# 1u_panel_breakout.net
KiCad netlist of a schematic drawn in EAGLE
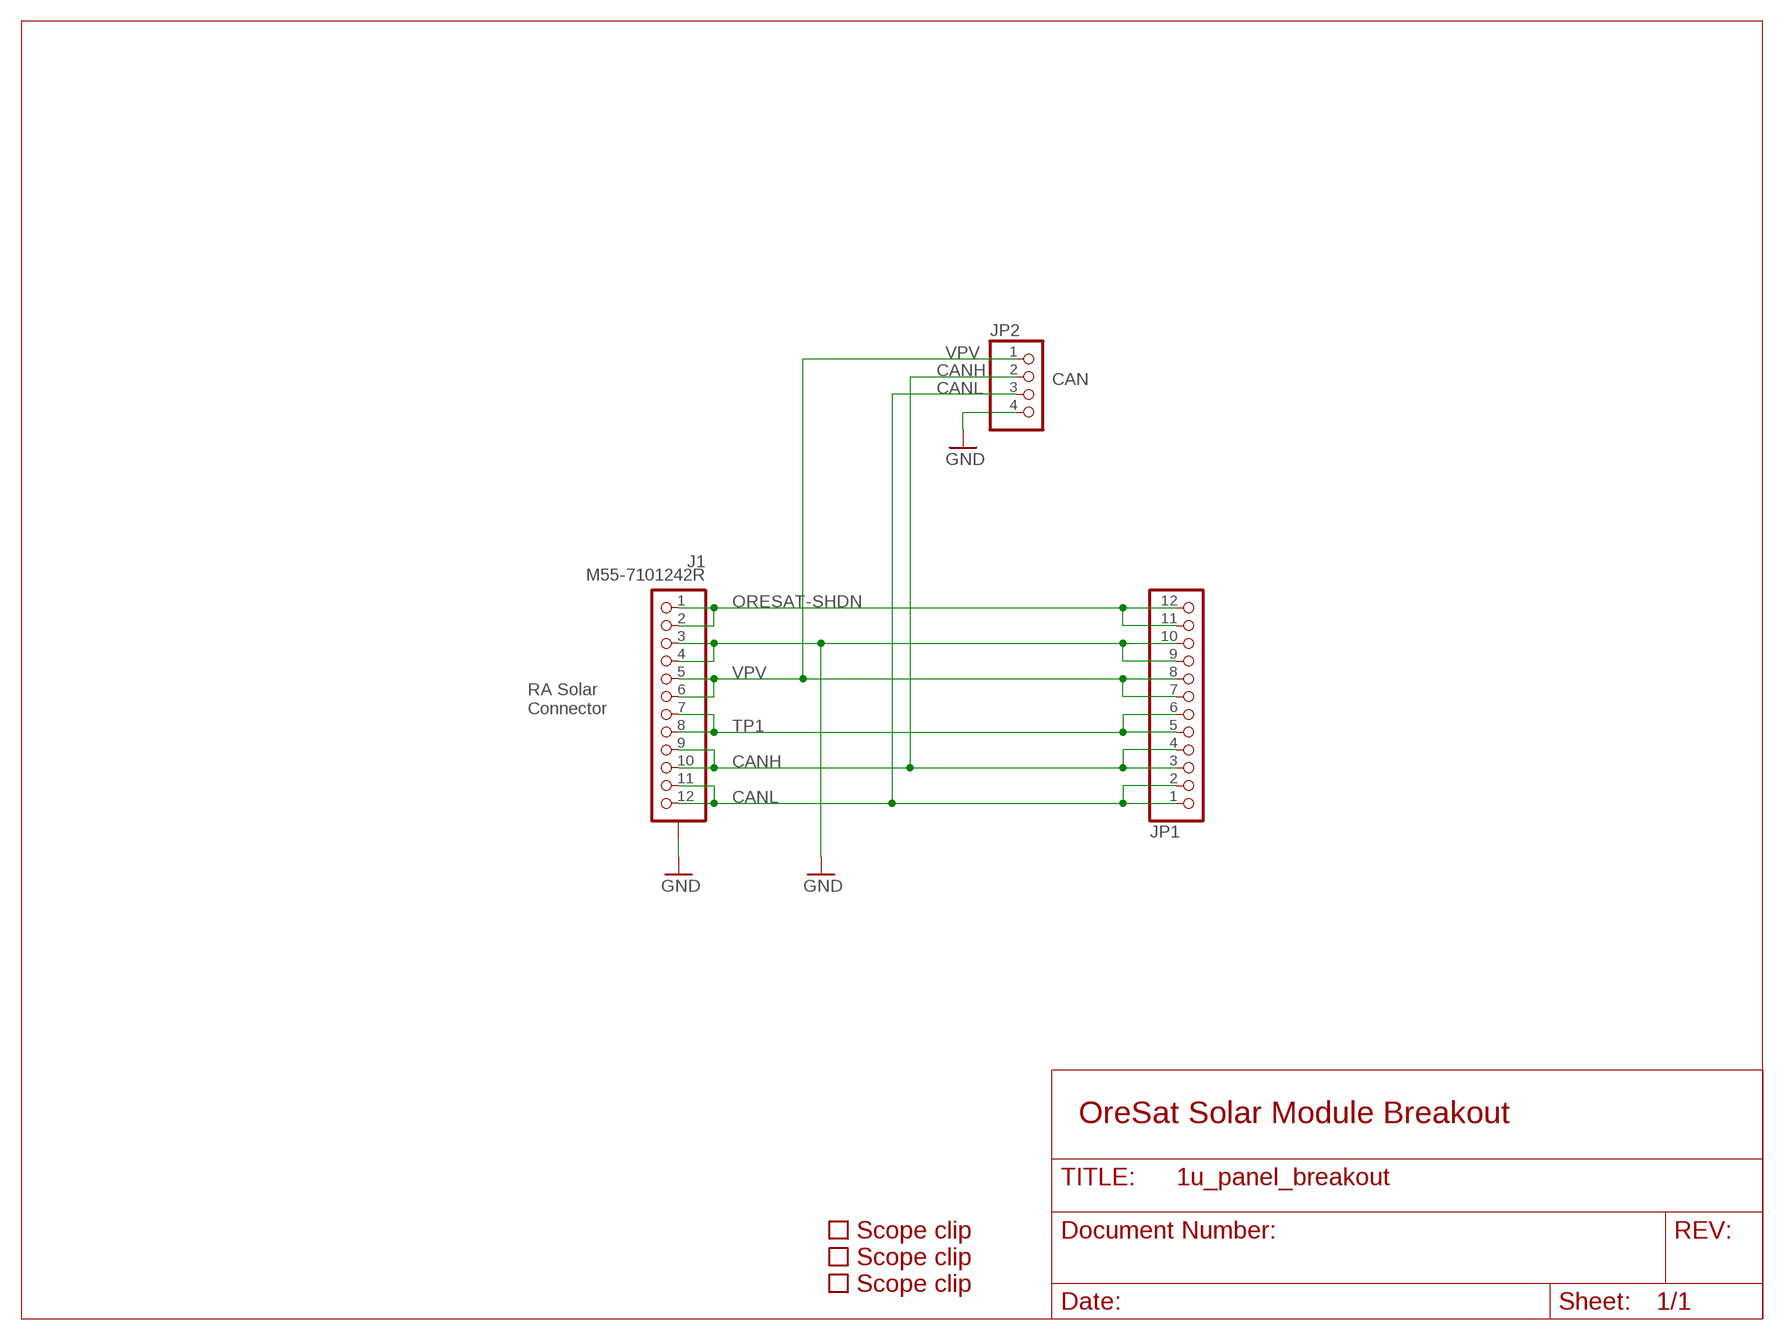
[diagram p0: schematic, sheet 1]

(export (version "E")
  (design (tool "Eeschema 10.0.6"))
  (components
    (comp (ref "J1")
      (value "M55-7101242R")
      (footprint "eagle-import:M55-7101242R")
      (libsource (lib "eagle-import") (part "M55-7101242R"))
    )
    (comp (ref "JP1")
      (value "PINHD-1X12")
      (footprint "eagle-import:1X12")
      (libsource (lib "eagle-import") (part "PINHD-1X12"))
    )
    (comp (ref "JP2")
      (value "PINHD-1X4")
      (footprint "eagle-import:1X04")
      (libsource (lib "eagle-import") (part "PINHD-1X4"))
    )
    (comp (ref "U$1")
      (value "SCOPE_CLIP")
      (footprint "eagle-import:SCOPE_CLIP")
      (libsource (lib "eagle-import") (part "SCOPE_CLIP"))
    )
    (comp (ref "U$2")
      (value "SCOPE_CLIP")
      (footprint "eagle-import:SCOPE_CLIP")
      (libsource (lib "eagle-import") (part "SCOPE_CLIP"))
    )
    (comp (ref "U$3")
      (value "SCOPE_CLIP")
      (footprint "eagle-import:SCOPE_CLIP")
      (libsource (lib "eagle-import") (part "SCOPE_CLIP"))
    )
  )
  (nets
    (net (code "1") (name "/CANH") (class "Default")
      (node (ref "J1") (pin "10") (pinfunction "10_10") (pintype "passive"))
      (node (ref "J1") (pin "9") (pinfunction "9_9") (pintype "passive"))
      (node (ref "JP1") (pin "3") (pinfunction "3_3") (pintype "passive"))
      (node (ref "JP1") (pin "4") (pinfunction "4_4") (pintype "passive"))
      (node (ref "JP2") (pin "2") (pinfunction "2_2") (pintype "passive"))
    )
    (net (code "2") (name "/CANL") (class "Default")
      (node (ref "J1") (pin "11") (pinfunction "11_11") (pintype "passive"))
      (node (ref "J1") (pin "12") (pinfunction "12_12") (pintype "passive"))
      (node (ref "JP1") (pin "1") (pinfunction "1_1") (pintype "passive"))
      (node (ref "JP1") (pin "2") (pinfunction "2_2") (pintype "passive"))
      (node (ref "JP2") (pin "3") (pinfunction "3_3") (pintype "passive"))
    )
    (net (code "3") (name "/ORESAT-SHDN") (class "Default")
      (node (ref "J1") (pin "1") (pinfunction "1_1") (pintype "passive"))
      (node (ref "J1") (pin "2") (pinfunction "2_2") (pintype "passive"))
      (node (ref "JP1") (pin "11") (pinfunction "11_11") (pintype "passive"))
      (node (ref "JP1") (pin "12") (pinfunction "12_12") (pintype "passive"))
    )
    (net (code "4") (name "/TP1") (class "Default")
      (node (ref "J1") (pin "7") (pinfunction "7_7") (pintype "passive"))
      (node (ref "J1") (pin "8") (pinfunction "8_8") (pintype "passive"))
      (node (ref "JP1") (pin "5") (pinfunction "5_5") (pintype "passive"))
      (node (ref "JP1") (pin "6") (pinfunction "6_6") (pintype "passive"))
    )
    (net (code "5") (name "/VPV") (class "Default")
      (node (ref "J1") (pin "5") (pinfunction "5_5") (pintype "passive"))
      (node (ref "J1") (pin "6") (pinfunction "6_6") (pintype "passive"))
      (node (ref "JP1") (pin "7") (pinfunction "7_7") (pintype "passive"))
      (node (ref "JP1") (pin "8") (pinfunction "8_8") (pintype "passive"))
      (node (ref "JP2") (pin "1") (pinfunction "1_1") (pintype "passive"))
    )
    (net (code "6") (name "GND") (class "Default")
      (node (ref "J1") (pin "3") (pinfunction "3_3") (pintype "passive"))
      (node (ref "J1") (pin "4") (pinfunction "4_4") (pintype "passive"))
      (node (ref "J1") (pin "P$1") (pinfunction "SHIELD_P$1") (pintype "passive"))
      (node (ref "J1") (pin "P$2") (pinfunction "SHIELD_P$2") (pintype "passive"))
      (node (ref "J1") (pin "P$3") (pinfunction "SHIELD_P$3") (pintype "passive"))
      (node (ref "J1") (pin "P$4") (pinfunction "SHIELD_P$4") (pintype "passive"))
      (node (ref "JP1") (pin "10") (pinfunction "10_10") (pintype "passive"))
      (node (ref "JP1") (pin "9") (pinfunction "9_9") (pintype "passive"))
      (node (ref "JP2") (pin "4") (pinfunction "4_4") (pintype "passive"))
    )
  )
)
